# OVP.net
KiCad netlist of a schematic drawn in Altium Designer
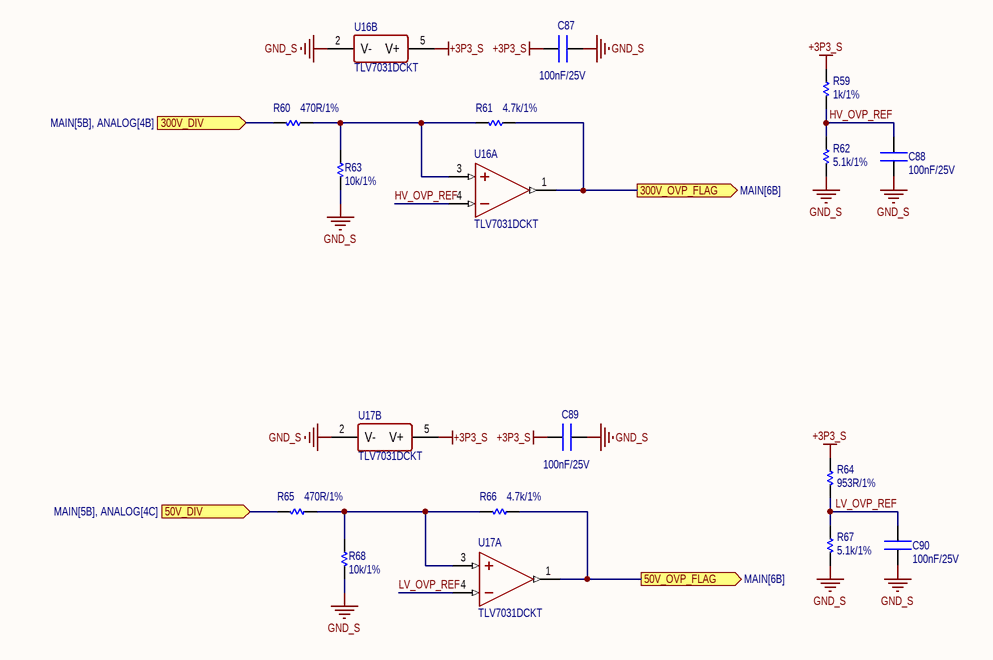
[diagram p0: OVP.SchDoc]

(export (version "E")
  (design (tool "Eeschema 10.0.6"))
  (components
    (comp (ref "C87")
      (value "100nF/25V")
      (footprint "CN-SMD-0603")
      (description "CAP CER 0.1UF 25V X7R 0603")
      (libsource (lib "Library") (part "CN"))
    )
    (comp (ref "C88")
      (value "100nF/25V")
      (footprint "CN-SMD-0603")
      (description "CAP CER 0.1UF 25V X7R 0603")
      (libsource (lib "Library") (part "CN"))
    )
    (comp (ref "C89")
      (value "100nF/25V")
      (footprint "CN-SMD-0603")
      (description "CAP CER 0.1UF 25V X7R 0603")
      (libsource (lib "Library") (part "CN"))
    )
    (comp (ref "C90")
      (value "100nF/25V")
      (footprint "CN-SMD-0603")
      (description "CAP CER 0.1UF 25V X7R 0603")
      (libsource (lib "Library") (part "CN"))
    )
    (comp (ref "R59")
      (value "1k/1%")
      (footprint "RES-SMD-0603")
      (description "RES SMD 1K OHM 1% 1/10W 0603")
      (fields
        (field (name "MANUFACTURER") "Generic Components")
        (field (name "PUBLISHER") "Altium Hobart Technology Centre")
      )
      (libsource (lib "Library") (part "Res-SMD"))
    )
    (comp (ref "R60")
      (value "470R/1%")
      (footprint "RES-SMD-0603")
      (description "RES 470 OHM 1% 1/10W 0603")
      (fields
        (field (name "MANUFACTURER") "Generic Components")
        (field (name "PUBLISHER") "Altium Hobart Technology Centre")
      )
      (libsource (lib "Library") (part "Res-SMD"))
    )
    (comp (ref "R61")
      (value "4.7k/1%")
      (footprint "RES-SMD-0603")
      (description "RES SMD 4.7K OHM 1% 1/10W 0603")
      (fields
        (field (name "MANUFACTURER") "Generic Components")
        (field (name "PUBLISHER") "Altium Hobart Technology Centre")
      )
      (libsource (lib "Library") (part "Res-SMD"))
    )
    (comp (ref "R62")
      (value "5.1k/1%")
      (footprint "RES-SMD-0603")
      (description "RES SMD 5.1K OHM 1% 1/10W 0603")
      (fields
        (field (name "MANUFACTURER") "Generic Components")
        (field (name "PUBLISHER") "Altium Hobart Technology Centre")
      )
      (libsource (lib "Library") (part "Res-SMD"))
    )
    (comp (ref "R63")
      (value "10k/1%")
      (footprint "RES-SMD-0603")
      (description "RES SMD 10K OHM 1% 1/10W 0603")
      (fields
        (field (name "MANUFACTURER") "Generic Components")
        (field (name "PUBLISHER") "Altium Hobart Technology Centre")
      )
      (libsource (lib "Library") (part "Res-SMD"))
    )
    (comp (ref "R64")
      (value "953R/1%")
      (footprint "RES-SMD-0603")
      (description "RES SMD 953 OHM 1% 1/10W 0603")
      (fields
        (field (name "MANUFACTURER") "Generic Components")
        (field (name "PUBLISHER") "Altium Hobart Technology Centre")
      )
      (libsource (lib "Library") (part "Res-SMD"))
    )
    (comp (ref "R65")
      (value "470R/1%")
      (footprint "RES-SMD-0603")
      (description "RES 470 OHM 1% 1/10W 0603")
      (fields
        (field (name "MANUFACTURER") "Generic Components")
        (field (name "PUBLISHER") "Altium Hobart Technology Centre")
      )
      (libsource (lib "Library") (part "Res-SMD"))
    )
    (comp (ref "R66")
      (value "4.7k/1%")
      (footprint "RES-SMD-0603")
      (description "RES SMD 4.7K OHM 1% 1/10W 0603")
      (fields
        (field (name "MANUFACTURER") "Generic Components")
        (field (name "PUBLISHER") "Altium Hobart Technology Centre")
      )
      (libsource (lib "Library") (part "Res-SMD"))
    )
    (comp (ref "R67")
      (value "5.1k/1%")
      (footprint "RES-SMD-0603")
      (description "RES SMD 5.1K OHM 1% 1/10W 0603")
      (fields
        (field (name "MANUFACTURER") "Generic Components")
        (field (name "PUBLISHER") "Altium Hobart Technology Centre")
      )
      (libsource (lib "Library") (part "Res-SMD"))
    )
    (comp (ref "R68")
      (value "10k/1%")
      (footprint "RES-SMD-0603")
      (description "RES SMD 10K OHM 1% 1/10W 0603")
      (fields
        (field (name "MANUFACTURER") "Generic Components")
        (field (name "PUBLISHER") "Altium Hobart Technology Centre")
      )
      (libsource (lib "Library") (part "Res-SMD"))
    )
    (comp (ref "U16")
      (value "TLV7031DCKT")
      (footprint "SOT353")
      (description "IC COMPARATOR 1 GEN PUR SC70-5")
      (libsource (lib "Library") (part "OPA340DBV"))
    )
    (comp (ref "U17")
      (value "TLV7031DCKT")
      (footprint "SOT353")
      (description "IC COMPARATOR 1 GEN PUR SC70-5")
      (libsource (lib "Library") (part "OPA340DBV"))
    )
  )
  (nets
    (net (code "1") (name "+3P3_S") (class "Default")
      (node (ref "C87") (pin "1") (pinfunction "1_1") (pintype "passive"))
      (node (ref "C89") (pin "1") (pinfunction "1_1") (pintype "passive"))
      (node (ref "R59") (pin "1") (pinfunction "1_1") (pintype "passive"))
      (node (ref "R64") (pin "1") (pinfunction "1_1") (pintype "passive"))
      (node (ref "U16") (pin "5") (pinfunction "V+_5") (pintype "passive"))
      (node (ref "U17") (pin "5") (pinfunction "V+_5") (pintype "passive"))
    )
    (net (code "2") (name "/50V_DIV") (class "Default")
      (node (ref "R65") (pin "2") (pinfunction "2_2") (pintype "passive"))
    )
    (net (code "3") (name "/50V_OVP_FLAG") (class "Default")
      (node (ref "R66") (pin "1") (pinfunction "1_1") (pintype "passive"))
      (node (ref "U17") (pin "1") (pinfunction "OUT_1") (pintype "output"))
    )
    (net (code "4") (name "/300V_DIV") (class "Default")
      (node (ref "R60") (pin "2") (pinfunction "2_2") (pintype "passive"))
    )
    (net (code "5") (name "/300V_OVP_FLAG") (class "Default")
      (node (ref "R61") (pin "1") (pinfunction "1_1") (pintype "passive"))
      (node (ref "U16") (pin "1") (pinfunction "OUT_1") (pintype "output"))
    )
    (net (code "6") (name "/HV_OVP_REF") (class "Default")
      (node (ref "C88") (pin "2") (pinfunction "2_2") (pintype "passive"))
      (node (ref "R59") (pin "2") (pinfunction "2_2") (pintype "passive"))
      (node (ref "R62") (pin "1") (pinfunction "1_1") (pintype "passive"))
      (node (ref "U16") (pin "4") (pinfunction "IN-_4") (pintype "input"))
    )
    (net (code "7") (name "/LV_OVP_REF") (class "Default")
      (node (ref "C90") (pin "2") (pinfunction "2_2") (pintype "passive"))
      (node (ref "R64") (pin "2") (pinfunction "2_2") (pintype "passive"))
      (node (ref "R67") (pin "1") (pinfunction "1_1") (pintype "passive"))
      (node (ref "U17") (pin "4") (pinfunction "IN-_4") (pintype "input"))
    )
    (net (code "8") (name "GND_S") (class "Default")
      (node (ref "C87") (pin "2") (pinfunction "2_2") (pintype "passive"))
      (node (ref "C88") (pin "1") (pinfunction "1_1") (pintype "passive"))
      (node (ref "C89") (pin "2") (pinfunction "2_2") (pintype "passive"))
      (node (ref "C90") (pin "1") (pinfunction "1_1") (pintype "passive"))
      (node (ref "R62") (pin "2") (pinfunction "2_2") (pintype "passive"))
      (node (ref "R63") (pin "2") (pinfunction "2_2") (pintype "passive"))
      (node (ref "R67") (pin "2") (pinfunction "2_2") (pintype "passive"))
      (node (ref "R68") (pin "2") (pinfunction "2_2") (pintype "passive"))
      (node (ref "U16") (pin "2") (pinfunction "V-_2") (pintype "passive"))
      (node (ref "U17") (pin "2") (pinfunction "V-_2") (pintype "passive"))
    )
    (net (code "9") (name "Net-(U16A-IN+)") (class "Default")
      (node (ref "R60") (pin "1") (pinfunction "1_1") (pintype "passive"))
      (node (ref "R61") (pin "2") (pinfunction "2_2") (pintype "passive"))
      (node (ref "R63") (pin "1") (pinfunction "1_1") (pintype "passive"))
      (node (ref "U16") (pin "3") (pinfunction "IN+_3") (pintype "input"))
    )
    (net (code "10") (name "Net-(U17A-IN+)") (class "Default")
      (node (ref "R65") (pin "1") (pinfunction "1_1") (pintype "passive"))
      (node (ref "R66") (pin "2") (pinfunction "2_2") (pintype "passive"))
      (node (ref "R68") (pin "1") (pinfunction "1_1") (pintype "passive"))
      (node (ref "U17") (pin "3") (pinfunction "IN+_3") (pintype "input"))
    )
  )
)
